# spi_rom.net
KiCad netlist of a schematic drawn in EAGLE
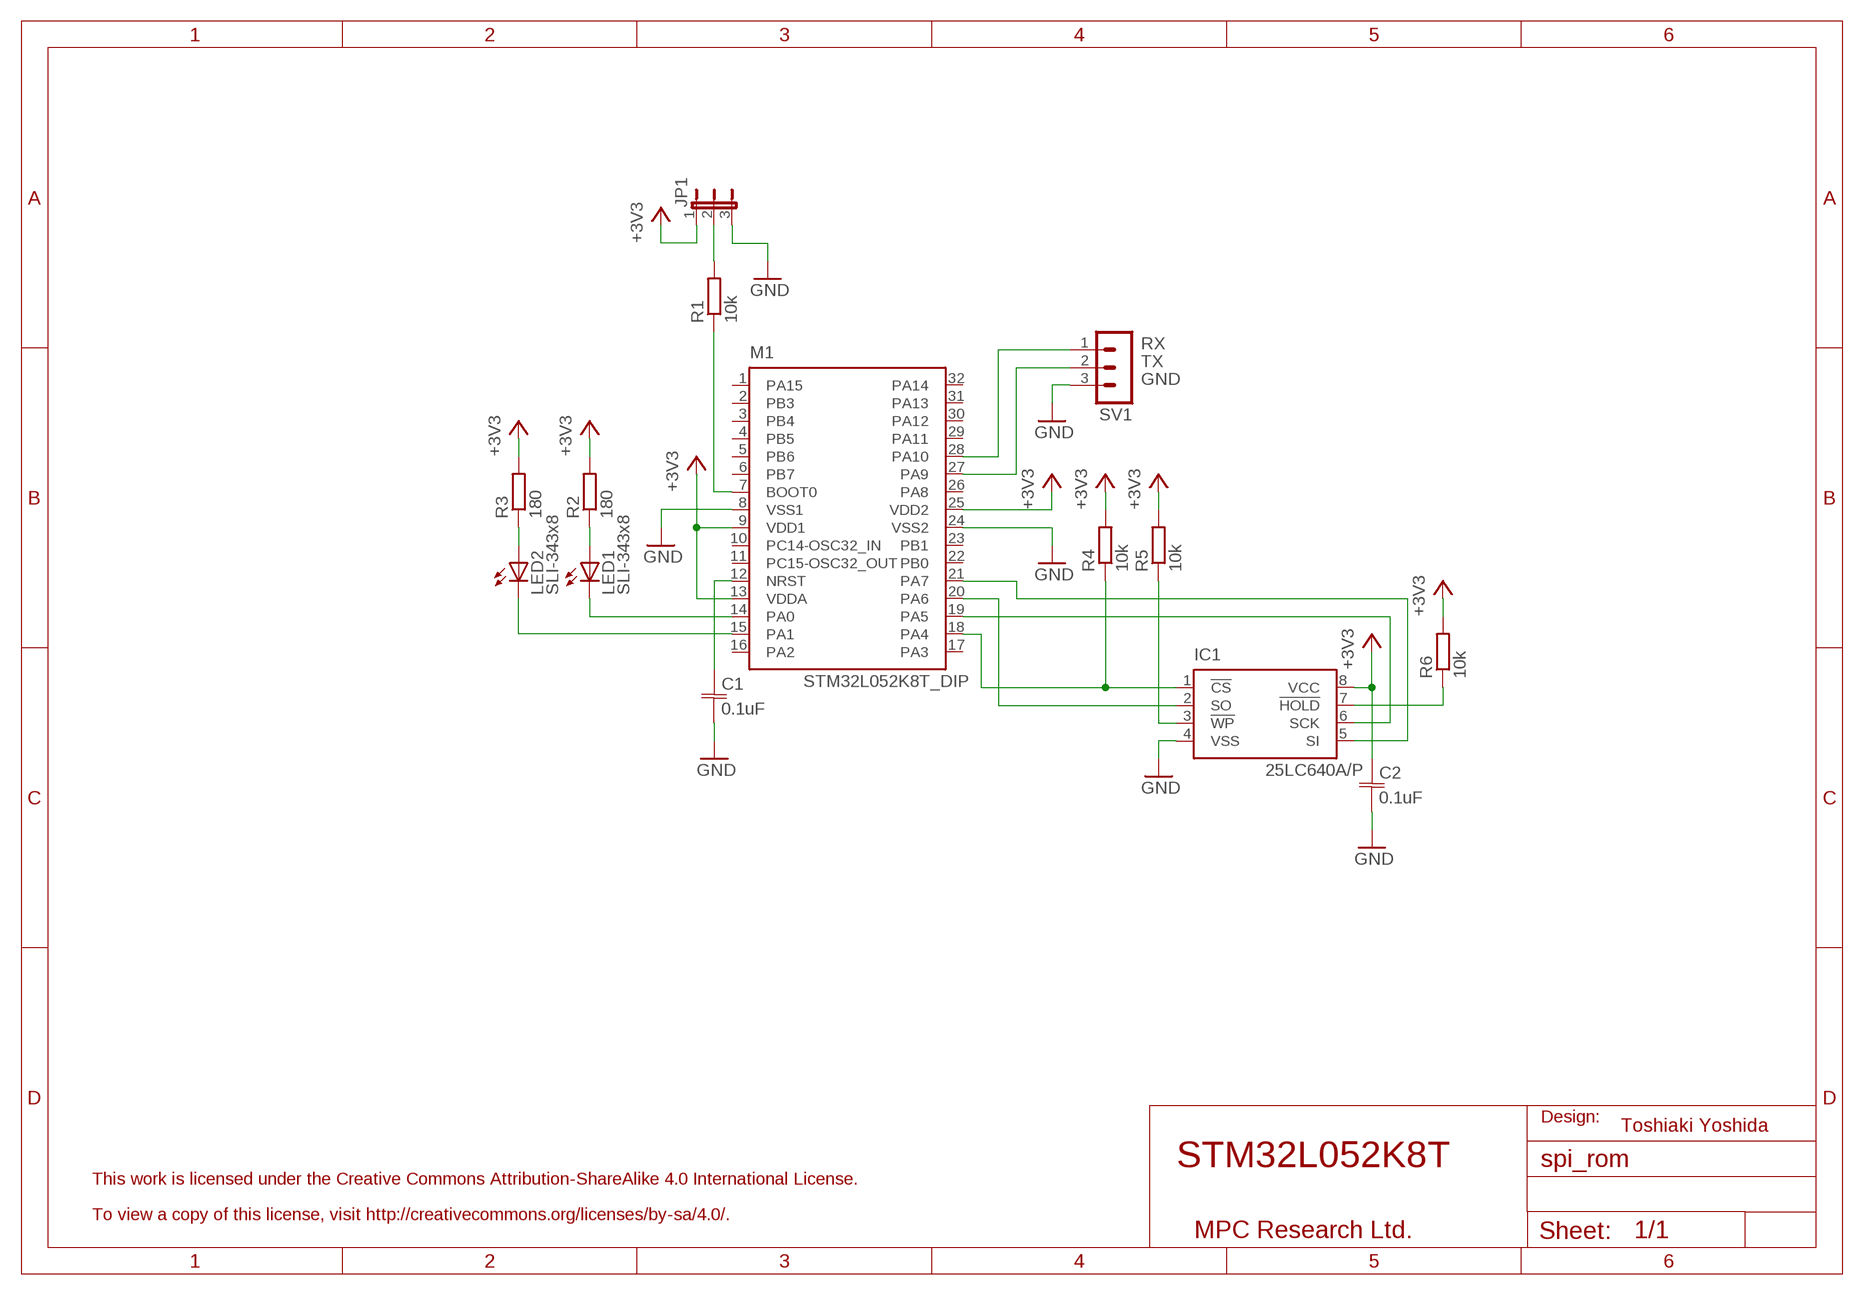
[diagram p0: schematic, sheet 1]

(export (version "E")
  (design (tool "Eeschema 10.0.6"))
  (components
    (comp (ref "C1")
      (value "0.1uF")
      (footprint "eagle-import:C050-024X044")
      (libsource (lib "eagle-import") (part "C-JIS050-024X044"))
    )
    (comp (ref "C2")
      (value "0.1uF")
      (footprint "eagle-import:C050-024X044")
      (libsource (lib "eagle-import") (part "C-JIS050-024X044"))
    )
    (comp (ref "IC1")
      (value "25LC640A/P")
      (footprint "eagle-import:DIL8")
      (libsource (lib "eagle-import") (part "25/PLC640A"))
    )
    (comp (ref "JP1")
      (value "JP2E")
      (footprint "eagle-import:JP2")
      (libsource (lib "eagle-import") (part "JP2E"))
    )
    (comp (ref "LED1")
      (value "SLI-343x8")
      (footprint "eagle-import:LED3MM")
      (libsource (lib "eagle-import") (part "LED3MM"))
    )
    (comp (ref "LED2")
      (value "SLI-343x8")
      (footprint "eagle-import:LED3MM")
      (libsource (lib "eagle-import") (part "LED3MM"))
    )
    (comp (ref "M1")
      (value "STM32L052K8T_DIP")
      (footprint "eagle-import:DIP32")
      (libsource (lib "eagle-import") (part "STM32L052K8T_DIP"))
    )
    (comp (ref "R1")
      (value "10k")
      (footprint "eagle-import:0207_2V")
      (libsource (lib "eagle-import") (part "R-EU_0207/2V"))
    )
    (comp (ref "R2")
      (value "180")
      (footprint "eagle-import:0207_2V")
      (libsource (lib "eagle-import") (part "R-EU_0207/2V"))
    )
    (comp (ref "R3")
      (value "180")
      (footprint "eagle-import:0207_2V")
      (libsource (lib "eagle-import") (part "R-EU_0207/2V"))
    )
    (comp (ref "R4")
      (value "10k")
      (footprint "eagle-import:0207_2V")
      (libsource (lib "eagle-import") (part "R-EU_0207/2V"))
    )
    (comp (ref "R5")
      (value "10k")
      (footprint "eagle-import:0207_2V")
      (libsource (lib "eagle-import") (part "R-EU_0207/2V"))
    )
    (comp (ref "R6")
      (value "10k")
      (footprint "eagle-import:0207_2V")
      (libsource (lib "eagle-import") (part "R-EU_0207/2V"))
    )
    (comp (ref "SV1")
      (value "MA03-1")
      (footprint "eagle-import:MA03-1")
      (libsource (lib "eagle-import") (part "MA03-1"))
    )
  )
  (nets
    (net (code "1") (name "+3V3") (class "Default")
      (node (ref "C2") (pin "1") (pinfunction "1_1") (pintype "passive"))
      (node (ref "IC1") (pin "8") (pinfunction "VCC_8") (pintype "power_in"))
      (node (ref "JP1") (pin "1") (pinfunction "1_1") (pintype "passive"))
      (node (ref "M1") (pin "13") (pinfunction "VDDA_13") (pintype "power_in"))
      (node (ref "M1") (pin "25") (pinfunction "VDD2_25") (pintype "bidirectional"))
      (node (ref "M1") (pin "9") (pinfunction "VDD1_9") (pintype "power_in"))
      (node (ref "R2") (pin "2") (pinfunction "2_2") (pintype "passive"))
      (node (ref "R3") (pin "2") (pinfunction "2_2") (pintype "passive"))
      (node (ref "R4") (pin "2") (pinfunction "2_2") (pintype "passive"))
      (node (ref "R5") (pin "2") (pinfunction "2_2") (pintype "passive"))
      (node (ref "R6") (pin "2") (pinfunction "2_2") (pintype "passive"))
    )
    (net (code "2") (name "GND") (class "Default")
      (node (ref "C1") (pin "2") (pinfunction "2_2") (pintype "passive"))
      (node (ref "C2") (pin "2") (pinfunction "2_2") (pintype "passive"))
      (node (ref "IC1") (pin "4") (pinfunction "VSS_4") (pintype "power_in"))
      (node (ref "JP1") (pin "3") (pinfunction "3_3") (pintype "passive"))
      (node (ref "M1") (pin "24") (pinfunction "VSS2_24") (pintype "power_in"))
      (node (ref "M1") (pin "8") (pinfunction "VSS1_8") (pintype "power_in"))
      (node (ref "SV1") (pin "3") (pinfunction "3_3") (pintype "passive"))
    )
    (net (code "3") (name "Net-(IC1-SCK)") (class "Default")
      (node (ref "IC1") (pin "6") (pinfunction "SCK_6") (pintype "input"))
      (node (ref "M1") (pin "19") (pinfunction "PA5_19") (pintype "bidirectional"))
    )
    (net (code "4") (name "Net-(IC1-SI)") (class "Default")
      (node (ref "IC1") (pin "5") (pinfunction "SI_5") (pintype "input"))
      (node (ref "M1") (pin "21") (pinfunction "PA7_21") (pintype "bidirectional"))
    )
    (net (code "5") (name "Net-(IC1-SO)") (class "Default")
      (node (ref "IC1") (pin "2") (pinfunction "SO_2") (pintype "output"))
      (node (ref "M1") (pin "20") (pinfunction "PA6_20") (pintype "bidirectional"))
    )
    (net (code "6") (name "Net-(IC1-~{CS})") (class "Default")
      (node (ref "IC1") (pin "1") (pinfunction "~{CS}_1") (pintype "input"))
      (node (ref "M1") (pin "18") (pinfunction "PA4_18") (pintype "bidirectional"))
      (node (ref "R4") (pin "1") (pinfunction "1_1") (pintype "passive"))
    )
    (net (code "7") (name "Net-(IC1-~{HOLD})") (class "Default")
      (node (ref "IC1") (pin "7") (pinfunction "~{HOLD}_7") (pintype "input"))
      (node (ref "R6") (pin "1") (pinfunction "1_1") (pintype "passive"))
    )
    (net (code "8") (name "Net-(IC1-~{WP})") (class "Default")
      (node (ref "IC1") (pin "3") (pinfunction "~{WP}_3") (pintype "input"))
      (node (ref "R5") (pin "1") (pinfunction "1_1") (pintype "passive"))
    )
    (net (code "9") (name "Net-(JP1-Pad2)") (class "Default")
      (node (ref "JP1") (pin "2") (pinfunction "2_2") (pintype "passive"))
      (node (ref "R1") (pin "2") (pinfunction "2_2") (pintype "passive"))
    )
    (net (code "10") (name "Net-(LED1-C)") (class "Default")
      (node (ref "LED1") (pin "K") (pinfunction "C_K") (pintype "passive"))
      (node (ref "M1") (pin "14") (pinfunction "PA0_14") (pintype "bidirectional"))
    )
    (net (code "11") (name "Net-(LED1-PadA)") (class "Default")
      (node (ref "LED1") (pin "A") (pinfunction "A_A") (pintype "passive"))
      (node (ref "R2") (pin "1") (pinfunction "1_1") (pintype "passive"))
    )
    (net (code "12") (name "Net-(LED2-C)") (class "Default")
      (node (ref "LED2") (pin "K") (pinfunction "C_K") (pintype "passive"))
      (node (ref "M1") (pin "15") (pinfunction "PA1_15") (pintype "bidirectional"))
    )
    (net (code "13") (name "Net-(LED2-PadA)") (class "Default")
      (node (ref "LED2") (pin "A") (pinfunction "A_A") (pintype "passive"))
      (node (ref "R3") (pin "1") (pinfunction "1_1") (pintype "passive"))
    )
    (net (code "14") (name "Net-(M1-BOOT0)") (class "Default")
      (node (ref "M1") (pin "7") (pinfunction "BOOT0_7") (pintype "bidirectional"))
      (node (ref "R1") (pin "1") (pinfunction "1_1") (pintype "passive"))
    )
    (net (code "15") (name "Net-(M1-NRST)") (class "Default")
      (node (ref "C1") (pin "1") (pinfunction "1_1") (pintype "passive"))
      (node (ref "M1") (pin "12") (pinfunction "NRST_12") (pintype "bidirectional"))
    )
    (net (code "16") (name "Net-(M1-PA9)") (class "Default")
      (node (ref "M1") (pin "27") (pinfunction "PA9_27") (pintype "bidirectional"))
      (node (ref "SV1") (pin "2") (pinfunction "2_2") (pintype "passive"))
    )
    (net (code "17") (name "Net-(M1-PA10)") (class "Default")
      (node (ref "M1") (pin "28") (pinfunction "PA10_28") (pintype "bidirectional"))
      (node (ref "SV1") (pin "1") (pinfunction "1_1") (pintype "passive"))
    )
    (net (code "18") (name "unconnected-(M1-PA2-Pad16)") (class "Default")
      (node (ref "M1") (pin "16") (pinfunction "PA2_16") (pintype "bidirectional"))
    )
    (net (code "19") (name "unconnected-(M1-PA3-Pad17)") (class "Default")
      (node (ref "M1") (pin "17") (pinfunction "PA3_17") (pintype "bidirectional"))
    )
    (net (code "20") (name "unconnected-(M1-PA8-Pad26)") (class "Default")
      (node (ref "M1") (pin "26") (pinfunction "PA8_26") (pintype "bidirectional"))
    )
    (net (code "21") (name "unconnected-(M1-PA11-Pad29)") (class "Default")
      (node (ref "M1") (pin "29") (pinfunction "PA11_29") (pintype "bidirectional"))
    )
    (net (code "22") (name "unconnected-(M1-PA12-Pad30)") (class "Default")
      (node (ref "M1") (pin "30") (pinfunction "PA12_30") (pintype "bidirectional"))
    )
    (net (code "23") (name "unconnected-(M1-PA13-Pad31)") (class "Default")
      (node (ref "M1") (pin "31") (pinfunction "PA13_31") (pintype "bidirectional"))
    )
    (net (code "24") (name "unconnected-(M1-PA14-Pad32)") (class "Default")
      (node (ref "M1") (pin "32") (pinfunction "PA14_32") (pintype "bidirectional"))
    )
    (net (code "25") (name "unconnected-(M1-PA15-Pad1)") (class "Default")
      (node (ref "M1") (pin "1") (pinfunction "PA15_1") (pintype "bidirectional"))
    )
    (net (code "26") (name "unconnected-(M1-PB0-Pad22)") (class "Default")
      (node (ref "M1") (pin "22") (pinfunction "PB0_22") (pintype "bidirectional"))
    )
    (net (code "27") (name "unconnected-(M1-PB1-Pad23)") (class "Default")
      (node (ref "M1") (pin "23") (pinfunction "PB1_23") (pintype "bidirectional"))
    )
    (net (code "28") (name "unconnected-(M1-PB3-Pad2)") (class "Default")
      (node (ref "M1") (pin "2") (pinfunction "PB3_2") (pintype "bidirectional"))
    )
    (net (code "29") (name "unconnected-(M1-PB4-Pad3)") (class "Default")
      (node (ref "M1") (pin "3") (pinfunction "PB4_3") (pintype "bidirectional"))
    )
    (net (code "30") (name "unconnected-(M1-PB5-Pad4)") (class "Default")
      (node (ref "M1") (pin "4") (pinfunction "PB5_4") (pintype "bidirectional"))
    )
    (net (code "31") (name "unconnected-(M1-PB6-Pad5)") (class "Default")
      (node (ref "M1") (pin "5") (pinfunction "PB6_5") (pintype "bidirectional"))
    )
    (net (code "32") (name "unconnected-(M1-PB7-Pad6)") (class "Default")
      (node (ref "M1") (pin "6") (pinfunction "PB7_6") (pintype "bidirectional"))
    )
    (net (code "33") (name "unconnected-(M1-PC14-OSC32_IN-Pad10)") (class "Default")
      (node (ref "M1") (pin "10") (pinfunction "PC14-OSC32_IN_10") (pintype "bidirectional"))
    )
    (net (code "34") (name "unconnected-(M1-PC15-OSC32_OUT-Pad11)") (class "Default")
      (node (ref "M1") (pin "11") (pinfunction "PC15-OSC32_OUT_11") (pintype "bidirectional"))
    )
  )
)
